# Metacarpal.net
KiCad netlist of a schematic drawn in Altium Designer
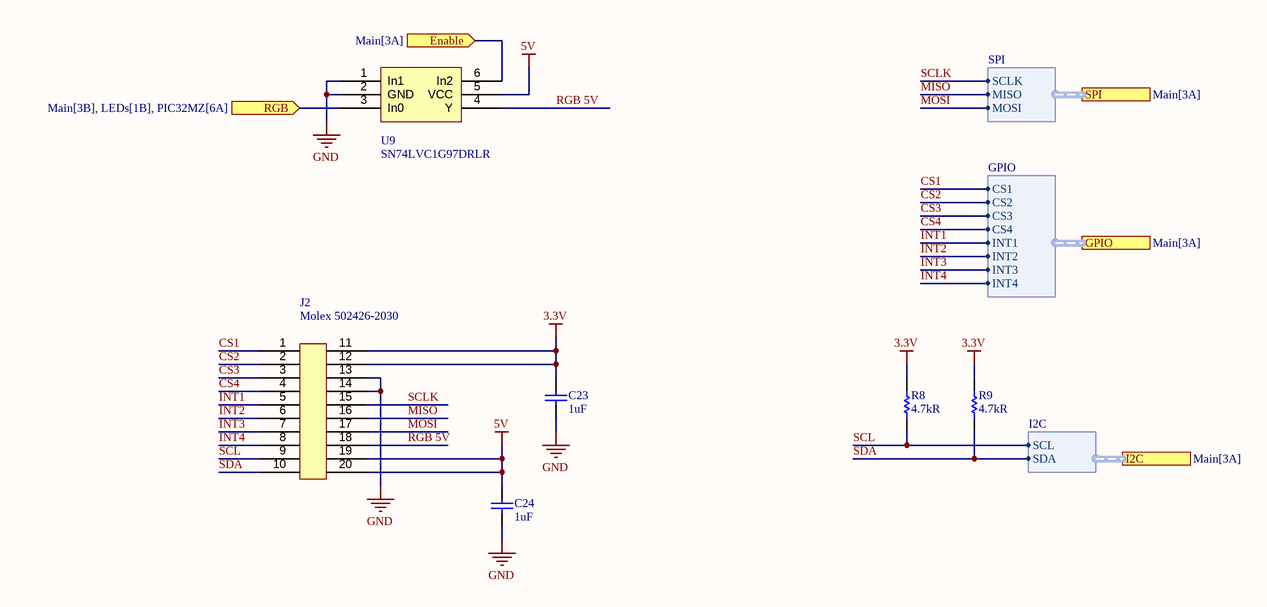
[diagram p0: Metacarpal.SchDoc]

(export (version "E")
  (design (tool "Eeschema 10.0.6"))
  (components
    (comp (ref "C23") (value "1uF") (footprint "Capacitor 0402") (libsource (lib "x-io") (part "Capacitor")))
    (comp (ref "C24") (value "1uF") (footprint "Capacitor 0402") (libsource (lib "x-io") (part "Capacitor")))
    (comp (ref "J2")
      (value "Molex 502426-2030")
      (footprint "Molex 502426-2030")
      (libsource (lib "x-io") (part "Molex 502426-2030"))
    )
    (comp (ref "R8") (value "4.7kR") (footprint "Resistor 0402") (libsource (lib "x-io") (part "Resistor")))
    (comp (ref "R9") (value "4.7kR") (footprint "Resistor 0402") (libsource (lib "x-io") (part "Resistor")))
    (comp (ref "U9")
      (value "SN74LVC1G97DRLR")
      (footprint "SOT-666")
      (libsource (lib "x-io") (part "SN74LVC1G97DRLR"))
    )
  )
  (nets
    (net (code "4") (name "/CS1") (class "Default")
      (node (ref "J2") (pin "1") (pinfunction "1_1") (pintype "passive"))
    )
    (net (code "5") (name "/CS2") (class "Default")
      (node (ref "J2") (pin "2") (pinfunction "2_2") (pintype "passive"))
    )
    (net (code "6") (name "/CS3") (class "Default")
      (node (ref "J2") (pin "3") (pinfunction "3_3") (pintype "passive"))
    )
    (net (code "7") (name "/CS4") (class "Default")
      (node (ref "J2") (pin "4") (pinfunction "4_4") (pintype "passive"))
    )
    (net (code "8") (name "/Enable") (class "Default")
      (node (ref "U9") (pin "6") (pinfunction "In2_6") (pintype "passive"))
    )
    (net (code "9") (name "/INT1") (class "Default")
      (node (ref "J2") (pin "5") (pinfunction "5_5") (pintype "passive"))
    )
    (net (code "10") (name "/INT2") (class "Default")
      (node (ref "J2") (pin "6") (pinfunction "6_6") (pintype "passive"))
    )
    (net (code "11") (name "/INT3") (class "Default")
      (node (ref "J2") (pin "7") (pinfunction "7_7") (pintype "passive"))
    )
    (net (code "12") (name "/INT4") (class "Default")
      (node (ref "J2") (pin "8") (pinfunction "8_8") (pintype "passive"))
    )
    (net (code "13") (name "/MISO") (class "Default")
      (node (ref "J2") (pin "16") (pinfunction "16_16") (pintype "passive"))
    )
    (net (code "14") (name "/MOSI") (class "Default")
      (node (ref "J2") (pin "17") (pinfunction "17_17") (pintype "passive"))
    )
    (net (code "15") (name "/RGB") (class "Default")
      (node (ref "U9") (pin "3") (pinfunction "In0_3") (pintype "passive"))
    )
    (net (code "16") (name "/RGB 5V") (class "Default")
      (node (ref "J2") (pin "18") (pinfunction "18_18") (pintype "passive"))
      (node (ref "U9") (pin "4") (pinfunction "Y_4") (pintype "passive"))
    )
    (net (code "17") (name "/SCL") (class "Default")
      (node (ref "J2") (pin "9") (pinfunction "9_9") (pintype "passive"))
      (node (ref "R8") (pin "1") (pinfunction "1_1") (pintype "passive"))
    )
    (net (code "18") (name "/SCLK") (class "Default")
      (node (ref "J2") (pin "15") (pinfunction "15_15") (pintype "passive"))
    )
    (net (code "19") (name "/SDA") (class "Default")
      (node (ref "J2") (pin "10") (pinfunction "10_10") (pintype "passive"))
      (node (ref "R9") (pin "1") (pinfunction "1_1") (pintype "passive"))
    )
    (net (code "23") (name "3.3V") (class "Default")
      (node (ref "C23") (pin "2") (pinfunction "2_2") (pintype "passive"))
      (node (ref "J2") (pin "11") (pinfunction "11_11") (pintype "passive"))
      (node (ref "J2") (pin "12") (pinfunction "12_12") (pintype "passive"))
      (node (ref "R8") (pin "2") (pinfunction "2_2") (pintype "passive"))
      (node (ref "R9") (pin "2") (pinfunction "2_2") (pintype "passive"))
    )
    (net (code "24") (name "5V") (class "Default")
      (node (ref "C24") (pin "2") (pinfunction "2_2") (pintype "passive"))
      (node (ref "J2") (pin "19") (pinfunction "19_19") (pintype "passive"))
      (node (ref "J2") (pin "20") (pinfunction "20_20") (pintype "passive"))
      (node (ref "U9") (pin "5") (pinfunction "VCC_5") (pintype "passive"))
    )
    (net (code "25") (name "GND") (class "Default")
      (node (ref "C23") (pin "1") (pinfunction "1_1") (pintype "passive"))
      (node (ref "C24") (pin "1") (pinfunction "1_1") (pintype "passive"))
      (node (ref "J2") (pin "13") (pinfunction "13_13") (pintype "passive"))
      (node (ref "J2") (pin "14") (pinfunction "14_14") (pintype "passive"))
      (node (ref "U9") (pin "1") (pinfunction "In1_1") (pintype "passive"))
      (node (ref "U9") (pin "2") (pinfunction "GND_2") (pintype "passive"))
    )
  )
)
